# feather-v1.net
KiCad netlist of a schematic drawn in EAGLE
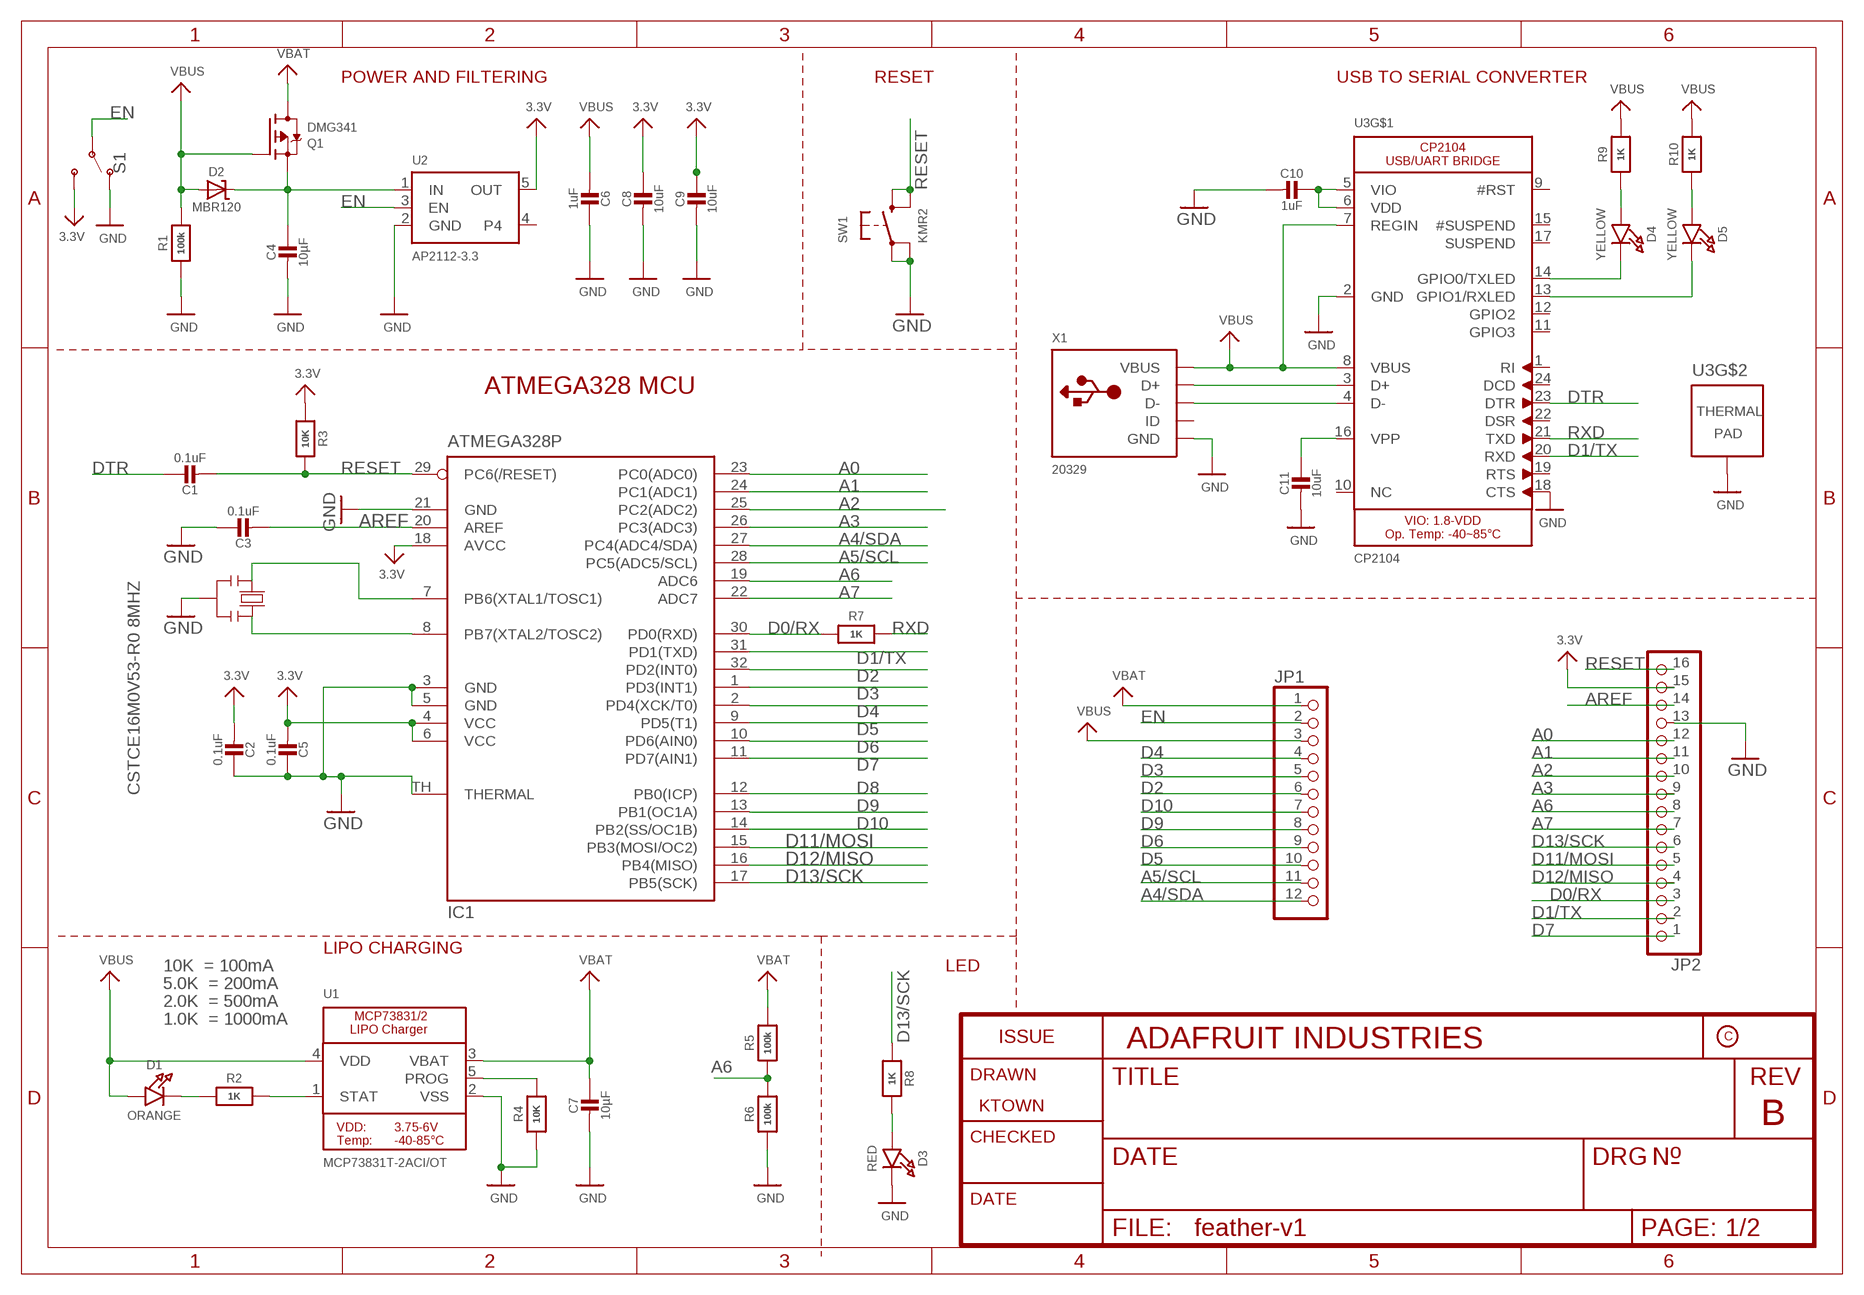
[diagram p0: schematic, sheet 1]
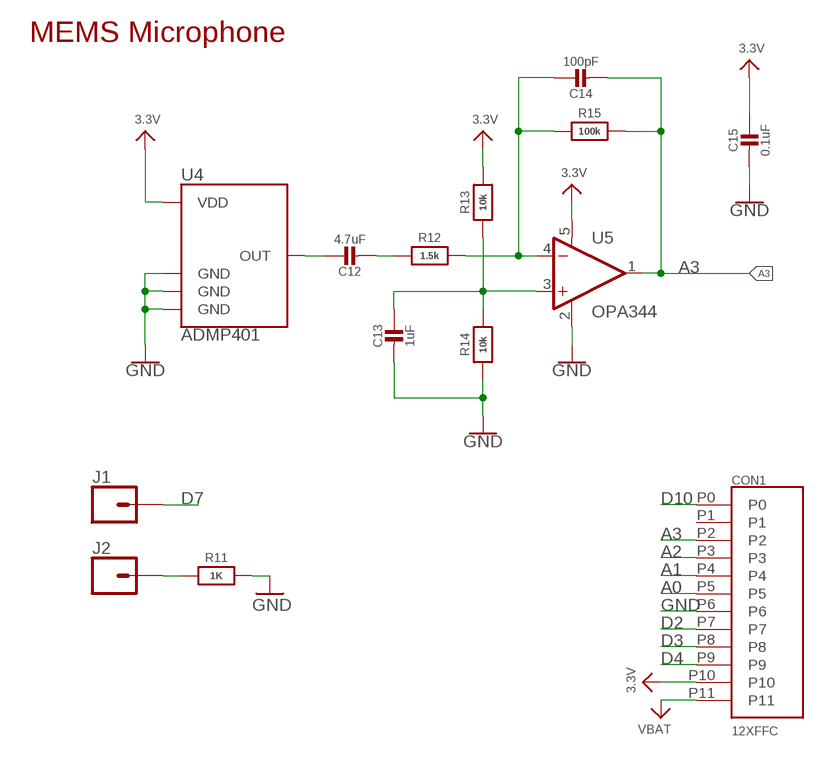
[diagram p1: schematic, sheet 2]

(export (version "E")
  (design (tool "Eeschema 10.0.6"))
  (components
    (comp (ref "C12")
      (value "4.7uF")
      (footprint "eagle-import:_0603MP")
      (libsource (lib "eagle-import") (part "CAP_CERAMIC_0603MP"))
    )
    (comp (ref "C13")
      (value "1uF")
      (footprint "eagle-import:_0603MP")
      (libsource (lib "eagle-import") (part "CAP_CERAMIC_0603MP"))
    )
    (comp (ref "C14")
      (value "100pF")
      (footprint "eagle-import:_0603MP")
      (libsource (lib "eagle-import") (part "CAP_CERAMIC_0603MP"))
    )
    (comp (ref "C15")
      (value "0.1uF")
      (footprint "eagle-import:_0603MP")
      (libsource (lib "eagle-import") (part "CAP_CERAMIC_0603MP"))
    )
    (comp (ref "CON1")
      (value "12XFFC")
      (footprint "eagle-import:15166-0117")
      (libsource (lib "eagle-import") (part "12XFFC"))
    )
    (comp (ref "J1")
      (value "CONN_01PTH_NO_SILK_YES_STOP")
      (footprint "eagle-import:1X01_NO_SILK")
      (libsource (lib "eagle-import") (part "CONN_01PTH_NO_SILK_YES_STOP"))
    )
    (comp (ref "J2")
      (value "CONN_01PTH_NO_SILK_YES_STOP")
      (footprint "eagle-import:1X01_NO_SILK")
      (libsource (lib "eagle-import") (part "CONN_01PTH_NO_SILK_YES_STOP"))
    )
    (comp (ref "R11")
      (value "1K")
      (footprint "eagle-import:_0603MP")
      (libsource (lib "eagle-import") (part "RESISTOR_0603MP"))
    )
    (comp (ref "R12")
      (value "1.5k")
      (footprint "eagle-import:_0603MP")
      (libsource (lib "eagle-import") (part "RESISTOR_0603MP"))
    )
    (comp (ref "R13")
      (value "10k")
      (footprint "eagle-import:_0603MP")
      (libsource (lib "eagle-import") (part "RESISTOR_0603MP"))
    )
    (comp (ref "R14")
      (value "10k")
      (footprint "eagle-import:_0603MP")
      (libsource (lib "eagle-import") (part "RESISTOR_0603MP"))
    )
    (comp (ref "R15")
      (value "100k")
      (footprint "eagle-import:_0603MP")
      (libsource (lib "eagle-import") (part "RESISTOR_0603MP"))
    )
    (comp (ref "U4")
      (value "ADMP401")
      (footprint "eagle-import:ADMP401")
      (libsource (lib "eagle-import") (part "ADMP401"))
    )
    (comp (ref "U5")
      (value "OPA344")
      (footprint "eagle-import:SOT23-5")
      (libsource (lib "eagle-import") (part "OPA344"))
    )
    (comp (ref "C1")
      (value "0.1uF")
      (footprint "eagle-import:_0603MP")
      (libsource (lib "eagle-import") (part "CAP_CERAMIC_0603MP"))
    )
    (comp (ref "C2")
      (value "0.1uF")
      (footprint "eagle-import:_0603MP")
      (libsource (lib "eagle-import") (part "CAP_CERAMIC_0603MP"))
    )
    (comp (ref "C3")
      (value "0.1uF")
      (footprint "eagle-import:_0603MP")
      (libsource (lib "eagle-import") (part "CAP_CERAMIC_0603MP"))
    )
    (comp (ref "C4")
      (value "10µF")
      (footprint "eagle-import:_0603MP")
      (libsource (lib "eagle-import") (part "CAP_CERAMIC_0603MP"))
    )
    (comp (ref "C5")
      (value "0.1uF")
      (footprint "eagle-import:_0603MP")
      (libsource (lib "eagle-import") (part "CAP_CERAMIC_0603MP"))
    )
    (comp (ref "C6")
      (value "1uF")
      (footprint "eagle-import:_0603MP")
      (libsource (lib "eagle-import") (part "CAP_CERAMIC_0603MP"))
    )
    (comp (ref "C7")
      (value "10µF")
      (footprint "eagle-import:_0603MP")
      (libsource (lib "eagle-import") (part "CAP_CERAMIC_0603MP"))
    )
    (comp (ref "C8")
      (value "10uF")
      (footprint "eagle-import:_0603MP")
      (libsource (lib "eagle-import") (part "CAP_CERAMIC_0603MP"))
    )
    (comp (ref "C9")
      (value "10uF")
      (footprint "eagle-import:_0603MP")
      (libsource (lib "eagle-import") (part "CAP_CERAMIC_0603MP"))
    )
    (comp (ref "C10")
      (value "1uF")
      (footprint "eagle-import:_0603MP")
      (libsource (lib "eagle-import") (part "CAP_CERAMIC_0603MP"))
    )
    (comp (ref "C11")
      (value "10uF")
      (footprint "eagle-import:_0603MP")
      (libsource (lib "eagle-import") (part "CAP_CERAMIC_0603MP"))
    )
    (comp (ref "D1")
      (value "ORANGE")
      (footprint "eagle-import:CHIPLED_0603_NOOUTLINE")
      (libsource (lib "eagle-import") (part "LED0603_NOOUTLINE"))
    )
    (comp (ref "D2")
      (value "MBR120")
      (footprint "eagle-import:SOD-523")
      (libsource (lib "eagle-import") (part "DIODE-SCHOTTKYSOD-523"))
    )
    (comp (ref "D3")
      (value "RED")
      (footprint "eagle-import:CHIPLED_0603_NOOUTLINE")
      (libsource (lib "eagle-import") (part "LED0603_NOOUTLINE"))
    )
    (comp (ref "D4")
      (value "YELLOW")
      (footprint "eagle-import:CHIPLED_0603_NOOUTLINE")
      (libsource (lib "eagle-import") (part "LED0603_NOOUTLINE"))
    )
    (comp (ref "D5")
      (value "YELLOW")
      (footprint "eagle-import:CHIPLED_0603_NOOUTLINE")
      (libsource (lib "eagle-import") (part "LED0603_NOOUTLINE"))
    )
    (comp (ref "IC1")
      (value "ATMEGA328P")
      (footprint "eagle-import:MLF32-TH")
      (fields (field (name "MPN") "ATMEGA88PA-MU"))
      (libsource (lib "eagle-import") (part "MEGA8-MI"))
    )
    (comp (ref "JP1")
      (value "HEADER-1X12")
      (footprint "eagle-import:1X12_ROUND")
      (libsource (lib "eagle-import") (part "HEADER-1X12"))
    )
    (comp (ref "JP2")
      (value "HEADER-1X16ROUND")
      (footprint "eagle-import:1X16_ROUND")
      (libsource (lib "eagle-import") (part "HEADER-1X16ROUND"))
    )
    (comp (ref "Q1")
      (value "DMG341")
      (footprint "eagle-import:SOT23-R")
      (libsource (lib "eagle-import") (part "MOSFET-P"))
    )
    (comp (ref "R1")
      (value "100k")
      (footprint "eagle-import:_0603MP")
      (libsource (lib "eagle-import") (part "RESISTOR_0603MP"))
    )
    (comp (ref "R2")
      (value "1K")
      (footprint "eagle-import:_0603MP")
      (libsource (lib "eagle-import") (part "RESISTOR_0603MP"))
    )
    (comp (ref "R3")
      (value "10K")
      (footprint "eagle-import:_0603MP")
      (libsource (lib "eagle-import") (part "RESISTOR_0603MP"))
    )
    (comp (ref "R4")
      (value "10K")
      (footprint "eagle-import:_0603MP")
      (libsource (lib "eagle-import") (part "RESISTOR_0603MP"))
    )
    (comp (ref "R5")
      (value "100k")
      (footprint "eagle-import:_0603MP")
      (libsource (lib "eagle-import") (part "RESISTOR_0603MP"))
    )
    (comp (ref "R6")
      (value "100k")
      (footprint "eagle-import:_0603MP")
      (libsource (lib "eagle-import") (part "RESISTOR_0603MP"))
    )
    (comp (ref "R7")
      (value "1K")
      (footprint "eagle-import:_0603MP")
      (libsource (lib "eagle-import") (part "RESISTOR_0603MP"))
    )
    (comp (ref "R8")
      (value "1K")
      (footprint "eagle-import:_0603MP")
      (libsource (lib "eagle-import") (part "RESISTOR_0603MP"))
    )
    (comp (ref "R9")
      (value "1K")
      (footprint "eagle-import:_0603MP")
      (libsource (lib "eagle-import") (part "RESISTOR_0603MP"))
    )
    (comp (ref "R10")
      (value "1K")
      (footprint "eagle-import:_0603MP")
      (libsource (lib "eagle-import") (part "RESISTOR_0603MP"))
    )
    (comp (ref "S1")
      (value "SWITCH-SPDT-SMD-RIGHT-ANGLE")
      (footprint "eagle-import:SWITCH_SPST_SMD_A")
      (libsource (lib "eagle-import") (part "SWITCH-SPDT-SMD-RIGHT-ANGLE"))
    )
    (comp (ref "SW1")
      (value "KMR2")
      (footprint "eagle-import:BTN_KMR2_4.6X2.8")
      (libsource (lib "eagle-import") (part "SWITCH_TACT_SMT4.6X2.8"))
    )
    (comp (ref "U1")
      (value "MCP73831T-2ACI/OT")
      (footprint "eagle-import:SOT23-5")
      (libsource (lib "eagle-import") (part "MCP73831/2"))
    )
    (comp (ref "U2")
      (value "AP2112-3.3")
      (footprint "eagle-import:SOT23-5")
      (libsource (lib "eagle-import") (part "VREG_SOT23-5"))
    )
    (comp (ref "U3")
      (value "CP2104")
      (footprint "eagle-import:QFN24_4MM_SMSC")
      (libsource (lib "eagle-import") (part "CP2104"))
    )
    (comp (ref "X1")
      (value "20329")
      (footprint "eagle-import:4UCONN_20329_V2")
      (libsource (lib "eagle-import") (part "USB_MICRO_20329_V2"))
    )
    (comp (ref "Y1")
      (value "CSTCE16M0V53-R0 8MHZ")
      (footprint "eagle-import:RESONATOR")
      (libsource (lib "eagle-import") (part "RESONATORMU"))
    )
  )
  (nets
    (net (code "1") (name "3.3V") (class "Default")
      (node (ref "C15") (pin "1") (pinfunction "1_1") (pintype "passive"))
      (node (ref "C2") (pin "2") (pinfunction "2_2") (pintype "passive"))
      (node (ref "C5") (pin "2") (pinfunction "2_2") (pintype "passive"))
      (node (ref "C8") (pin "1") (pinfunction "1_1") (pintype "passive"))
      (node (ref "C9") (pin "1") (pinfunction "1_1") (pintype "passive"))
      (node (ref "CON1") (pin "P10") (pinfunction "P10_P10") (pintype "bidirectional"))
      (node (ref "IC1") (pin "18") (pinfunction "AVCC_18") (pintype "power_in"))
      (node (ref "IC1") (pin "4") (pinfunction "VCC_4") (pintype "power_in"))
      (node (ref "IC1") (pin "6") (pinfunction "VCC_6") (pintype "power_in"))
      (node (ref "JP2") (pin "15") (pinfunction "15_15") (pintype "passive"))
      (node (ref "R13") (pin "2") (pinfunction "2_2") (pintype "passive"))
      (node (ref "R3") (pin "2") (pinfunction "2_2") (pintype "passive"))
      (node (ref "S1") (pin "3") (pinfunction "S_3") (pintype "passive"))
      (node (ref "U2") (pin "5") (pinfunction "OUT_5") (pintype "power_in"))
      (node (ref "U4") (pin "5") (pinfunction "VDD_5") (pintype "bidirectional"))
      (node (ref "U5") (pin "5") (pinfunction "V+_5") (pintype "power_in"))
    )
    (net (code "2") (name "A0") (class "Default")
      (node (ref "CON1") (pin "P5") (pinfunction "P5_P5") (pintype "bidirectional"))
      (node (ref "IC1") (pin "23") (pinfunction "PC0(ADC0)_23") (pintype "bidirectional"))
      (node (ref "JP2") (pin "12") (pinfunction "12_12") (pintype "passive"))
    )
    (net (code "3") (name "A1") (class "Default")
      (node (ref "CON1") (pin "P4") (pinfunction "P4_P4") (pintype "bidirectional"))
      (node (ref "IC1") (pin "24") (pinfunction "PC1(ADC1)_24") (pintype "bidirectional"))
      (node (ref "JP2") (pin "11") (pinfunction "11_11") (pintype "passive"))
    )
    (net (code "4") (name "A2") (class "Default")
      (node (ref "CON1") (pin "P3") (pinfunction "P3_P3") (pintype "bidirectional"))
      (node (ref "IC1") (pin "25") (pinfunction "PC2(ADC2)_25") (pintype "bidirectional"))
      (node (ref "JP2") (pin "10") (pinfunction "10_10") (pintype "passive"))
    )
    (net (code "5") (name "A3") (class "Default")
      (node (ref "C14") (pin "2") (pinfunction "2_2") (pintype "passive"))
      (node (ref "CON1") (pin "P2") (pinfunction "P2_P2") (pintype "bidirectional"))
      (node (ref "IC1") (pin "26") (pinfunction "PC3(ADC3)_26") (pintype "bidirectional"))
      (node (ref "JP2") (pin "9") (pinfunction "9_9") (pintype "passive"))
      (node (ref "R15") (pin "2") (pinfunction "2_2") (pintype "passive"))
      (node (ref "U5") (pin "1") (pinfunction "OUT_1") (pintype "output"))
    )
    (net (code "6") (name "A4{slash}SDA") (class "Default")
      (node (ref "IC1") (pin "27") (pinfunction "PC4(ADC4/SDA)_27") (pintype "bidirectional"))
      (node (ref "JP1") (pin "12") (pinfunction "12_12") (pintype "passive"))
    )
    (net (code "7") (name "A5{slash}SCL") (class "Default")
      (node (ref "IC1") (pin "28") (pinfunction "PC5(ADC5/SCL)_28") (pintype "bidirectional"))
      (node (ref "JP1") (pin "11") (pinfunction "11_11") (pintype "passive"))
    )
    (net (code "8") (name "A6") (class "Default")
      (node (ref "IC1") (pin "19") (pinfunction "ADC6_19") (pintype "bidirectional"))
      (node (ref "JP2") (pin "8") (pinfunction "8_8") (pintype "passive"))
      (node (ref "R5") (pin "1") (pinfunction "1_1") (pintype "passive"))
      (node (ref "R6") (pin "2") (pinfunction "2_2") (pintype "passive"))
    )
    (net (code "9") (name "A7") (class "Default")
      (node (ref "IC1") (pin "22") (pinfunction "ADC7_22") (pintype "bidirectional"))
      (node (ref "JP2") (pin "7") (pinfunction "7_7") (pintype "passive"))
    )
    (net (code "10") (name "AREF") (class "Default")
      (node (ref "C3") (pin "2") (pinfunction "2_2") (pintype "passive"))
      (node (ref "IC1") (pin "20") (pinfunction "AREF_20") (pintype "passive"))
      (node (ref "JP2") (pin "14") (pinfunction "14_14") (pintype "passive"))
    )
    (net (code "11") (name "D0{slash}RX") (class "Default")
      (node (ref "IC1") (pin "30") (pinfunction "PD0(RXD)_30") (pintype "bidirectional"))
      (node (ref "JP2") (pin "3") (pinfunction "3_3") (pintype "passive"))
      (node (ref "R7") (pin "1") (pinfunction "1_1") (pintype "passive"))
    )
    (net (code "12") (name "D1{slash}TX") (class "Default")
      (node (ref "IC1") (pin "31") (pinfunction "PD1(TXD)_31") (pintype "bidirectional"))
      (node (ref "JP2") (pin "2") (pinfunction "2_2") (pintype "passive"))
      (node (ref "U3") (pin "20") (pinfunction "RXD_20") (pintype "input"))
    )
    (net (code "13") (name "D2") (class "Default")
      (node (ref "CON1") (pin "P7") (pinfunction "P7_P7") (pintype "bidirectional"))
      (node (ref "IC1") (pin "32") (pinfunction "PD2(INT0)_32") (pintype "bidirectional"))
      (node (ref "JP1") (pin "6") (pinfunction "6_6") (pintype "passive"))
    )
    (net (code "14") (name "D3") (class "Default")
      (node (ref "CON1") (pin "P8") (pinfunction "P8_P8") (pintype "bidirectional"))
      (node (ref "IC1") (pin "1") (pinfunction "PD3(INT1)_1") (pintype "bidirectional"))
      (node (ref "JP1") (pin "5") (pinfunction "5_5") (pintype "passive"))
    )
    (net (code "15") (name "D4") (class "Default")
      (node (ref "CON1") (pin "P9") (pinfunction "P9_P9") (pintype "bidirectional"))
      (node (ref "IC1") (pin "2") (pinfunction "PD4(XCK/T0)_2") (pintype "bidirectional"))
      (node (ref "JP1") (pin "4") (pinfunction "4_4") (pintype "passive"))
    )
    (net (code "16") (name "D5") (class "Default")
      (node (ref "IC1") (pin "9") (pinfunction "PD5(T1)_9") (pintype "bidirectional"))
      (node (ref "JP1") (pin "10") (pinfunction "10_10") (pintype "passive"))
    )
    (net (code "17") (name "D6") (class "Default")
      (node (ref "IC1") (pin "10") (pinfunction "PD6(AIN0)_10") (pintype "bidirectional"))
      (node (ref "JP1") (pin "9") (pinfunction "9_9") (pintype "passive"))
    )
    (net (code "18") (name "D7") (class "Default")
      (node (ref "IC1") (pin "11") (pinfunction "PD7(AIN1)_11") (pintype "bidirectional"))
      (node (ref "J1") (pin "1") (pinfunction "1_1") (pintype "passive"))
      (node (ref "JP2") (pin "1") (pinfunction "1_1") (pintype "passive"))
    )
    (net (code "19") (name "D8") (class "Default")
      (node (ref "IC1") (pin "12") (pinfunction "PB0(ICP)_12") (pintype "bidirectional"))
    )
    (net (code "20") (name "D9") (class "Default")
      (node (ref "IC1") (pin "13") (pinfunction "PB1(OC1A)_13") (pintype "bidirectional"))
      (node (ref "JP1") (pin "8") (pinfunction "8_8") (pintype "passive"))
    )
    (net (code "21") (name "D10") (class "Default")
      (node (ref "CON1") (pin "P0") (pinfunction "P0_P0") (pintype "bidirectional"))
      (node (ref "IC1") (pin "14") (pinfunction "PB2(SS/OC1B)_14") (pintype "bidirectional"))
      (node (ref "JP1") (pin "7") (pinfunction "7_7") (pintype "passive"))
    )
    (net (code "22") (name "D11{slash}MOSI") (class "Default")
      (node (ref "IC1") (pin "15") (pinfunction "PB3(MOSI/OC2)_15") (pintype "bidirectional"))
      (node (ref "JP2") (pin "5") (pinfunction "5_5") (pintype "passive"))
    )
    (net (code "23") (name "D12{slash}MISO") (class "Default")
      (node (ref "IC1") (pin "16") (pinfunction "PB4(MISO)_16") (pintype "bidirectional"))
      (node (ref "JP2") (pin "4") (pinfunction "4_4") (pintype "passive"))
    )
    (net (code "24") (name "D13{slash}SCK") (class "Default")
      (node (ref "IC1") (pin "17") (pinfunction "PB5(SCK)_17") (pintype "bidirectional"))
      (node (ref "JP2") (pin "6") (pinfunction "6_6") (pintype "passive"))
      (node (ref "R8") (pin "1") (pinfunction "1_1") (pintype "passive"))
    )
    (net (code "25") (name "DTR") (class "Default")
      (node (ref "C1") (pin "1") (pinfunction "1_1") (pintype "passive"))
      (node (ref "U3") (pin "23") (pinfunction "DTR_23") (pintype "output"))
    )
    (net (code "26") (name "EN") (class "Default")
      (node (ref "JP1") (pin "2") (pinfunction "2_2") (pintype "passive"))
      (node (ref "S1") (pin "2") (pinfunction "P_2") (pintype "passive"))
      (node (ref "U2") (pin "3") (pinfunction "EN_3") (pintype "input"))
    )
    (net (code "27") (name "GND") (class "Default")
      (node (ref "C10") (pin "2") (pinfunction "2_2") (pintype "passive"))
      (node (ref "C11") (pin "2") (pinfunction "2_2") (pintype "passive"))
      (node (ref "C13") (pin "2") (pinfunction "2_2") (pintype "passive"))
      (node (ref "C15") (pin "2") (pinfunction "2_2") (pintype "passive"))
      (node (ref "C2") (pin "1") (pinfunction "1_1") (pintype "passive"))
      (node (ref "C3") (pin "1") (pinfunction "1_1") (pintype "passive"))
      (node (ref "C4") (pin "2") (pinfunction "2_2") (pintype "passive"))
      (node (ref "C5") (pin "1") (pinfunction "1_1") (pintype "passive"))
      (node (ref "C6") (pin "1") (pinfunction "1_1") (pintype "passive"))
      (node (ref "C7") (pin "2") (pinfunction "2_2") (pintype "passive"))
      (node (ref "C8") (pin "2") (pinfunction "2_2") (pintype "passive"))
      (node (ref "C9") (pin "2") (pinfunction "2_2") (pintype "passive"))
      (node (ref "CON1") (pin "P6") (pinfunction "P6_P6") (pintype "bidirectional"))
      (node (ref "D3") (pin "C") (pinfunction "C_C") (pintype "passive"))
      (node (ref "IC1") (pin "21") (pinfunction "GND_21") (pintype "power_in"))
      (node (ref "IC1") (pin "3") (pinfunction "GND_3") (pintype "power_in"))
      (node (ref "IC1") (pin "5") (pinfunction "GND_5") (pintype "power_in"))
      (node (ref "IC1") (pin "TH") (pinfunction "THERMAL_TH") (pintype "passive"))
      (node (ref "JP2") (pin "13") (pinfunction "13_13") (pintype "passive"))
      (node (ref "R1") (pin "1") (pinfunction "1_1") (pintype "passive"))
      (node (ref "R11") (pin "2") (pinfunction "2_2") (pintype "passive"))
      (node (ref "R14") (pin "1") (pinfunction "1_1") (pintype "passive"))
      (node (ref "R4") (pin "1") (pinfunction "1_1") (pintype "passive"))
      (node (ref "R6") (pin "1") (pinfunction "1_1") (pintype "passive"))
      (node (ref "S1") (pin "1") (pinfunction "O_1") (pintype "passive"))
      (node (ref "SW1") (pin "A") (pinfunction "P_A") (pintype "passive"))
      (node (ref "SW1") (pin "A'") (pinfunction "P1_A'") (pintype "passive"))
      (node (ref "U1") (pin "2") (pinfunction "VSS_2") (pintype "power_in"))
      (node (ref "U2") (pin "2") (pinfunction "GND_2") (pintype "power_in"))
      (node (ref "U3") (pin "18") (pinfunction "CTS_18") (pintype "input"))
      (node (ref "U3") (pin "2") (pinfunction "GND_2") (pintype "power_in"))
      (node (ref "U3") (pin "THERM") (pinfunction "TP_THERM") (pintype "power_in"))
      (node (ref "U4") (pin "2") (pinfunction "GND_2") (pintype "bidirectional"))
      (node (ref "U4") (pin "4") (pinfunction "GND_4") (pintype "bidirectional"))
      (node (ref "U4") (pin "6") (pinfunction "GND_6") (pintype "bidirectional"))
      (node (ref "U5") (pin "2") (pinfunction "V-_2") (pintype "power_in"))
      (node (ref "X1") (pin "BASE@1") (pinfunction "GND_BASE@1") (pintype "power_in"))
      (node (ref "X1") (pin "BASE@2") (pinfunction "GND_BASE@2") (pintype "power_in"))
      (node (ref "X1") (pin "GND") (pinfunction "GND_GND") (pintype "power_in"))
      (node (ref "X1") (pin "SPRT@1") (pinfunction "GND_SPRT@1") (pintype "power_in"))
      (node (ref "X1") (pin "SPRT@2") (pinfunction "GND_SPRT@2") (pintype "power_in"))
      (node (ref "X1") (pin "SPRT@3") (pinfunction "GND_SPRT@3") (pintype "power_in"))
      (node (ref "X1") (pin "SPRT@4") (pinfunction "GND_SPRT@4") (pintype "power_in"))
      (node (ref "Y1") (pin "2") (pinfunction "2_2") (pintype "passive"))
    )
    (net (code "28") (name "Net-(C12-Pad2)") (class "Default")
      (node (ref "C12") (pin "2") (pinfunction "2_2") (pintype "passive"))
      (node (ref "R12") (pin "1") (pinfunction "1_1") (pintype "passive"))
    )
    (net (code "29") (name "Net-(D1-PadC)") (class "Default")
      (node (ref "D1") (pin "C") (pinfunction "C_C") (pintype "passive"))
      (node (ref "R2") (pin "1") (pinfunction "1_1") (pintype "passive"))
    )
    (net (code "30") (name "Net-(D2-C)") (class "Default")
      (node (ref "C4") (pin "1") (pinfunction "1_1") (pintype "passive"))
      (node (ref "D2") (pin "K") (pinfunction "C_K") (pintype "passive"))
      (node (ref "Q1") (pin "2") (pinfunction "S_2") (pintype "passive"))
      (node (ref "U2") (pin "1") (pinfunction "IN_1") (pintype "power_in"))
    )
    (net (code "31") (name "Net-(D3-PadA)") (class "Default")
      (node (ref "D3") (pin "A") (pinfunction "A_A") (pintype "passive"))
      (node (ref "R8") (pin "2") (pinfunction "2_2") (pintype "passive"))
    )
    (net (code "32") (name "Net-(D4-PadA)") (class "Default")
      (node (ref "D4") (pin "A") (pinfunction "A_A") (pintype "passive"))
      (node (ref "R9") (pin "1") (pinfunction "1_1") (pintype "passive"))
    )
    (net (code "33") (name "Net-(D5-PadA)") (class "Default")
      (node (ref "D5") (pin "A") (pinfunction "A_A") (pintype "passive"))
      (node (ref "R10") (pin "1") (pinfunction "1_1") (pintype "passive"))
    )
    (net (code "34") (name "Net-(IC1-PB6(XTAL1{slash}TOSC1))") (class "Default")
      (node (ref "IC1") (pin "7") (pinfunction "PB6(XTAL1/TOSC1)_7") (pintype "bidirectional"))
      (node (ref "Y1") (pin "1") (pinfunction "1_1") (pintype "passive"))
    )
    (net (code "35") (name "Net-(IC1-PB7(XTAL2{slash}TOSC2))") (class "Default")
      (node (ref "IC1") (pin "8") (pinfunction "PB7(XTAL2/TOSC2)_8") (pintype "bidirectional"))
      (node (ref "Y1") (pin "3") (pinfunction "3_3") (pintype "passive"))
    )
    (net (code "36") (name "Net-(J2-Pad1)") (class "Default")
      (node (ref "J2") (pin "1") (pinfunction "1_1") (pintype "passive"))
      (node (ref "R11") (pin "1") (pinfunction "1_1") (pintype "passive"))
    )
    (net (code "37") (name "Net-(U1-PROG)") (class "Default")
      (node (ref "R4") (pin "2") (pinfunction "2_2") (pintype "passive"))
      (node (ref "U1") (pin "5") (pinfunction "PROG_5") (pintype "input"))
    )
    (net (code "38") (name "Net-(U1-STAT)") (class "Default")
      (node (ref "R2") (pin "2") (pinfunction "2_2") (pintype "passive"))
      (node (ref "U1") (pin "1") (pinfunction "STAT_1") (pintype "output"))
    )
    (net (code "39") (name "Net-(U3A-D+)") (class "Default")
      (node (ref "U3") (pin "3") (pinfunction "D+_3") (pintype "bidirectional"))
      (node (ref "X1") (pin "D+") (pinfunction "D+_D+") (pintype "bidirectional"))
    )
    (net (code "40") (name "Net-(U3A-D-)") (class "Default")
      (node (ref "U3") (pin "4") (pinfunction "D-_4") (pintype "bidirectional"))
      (node (ref "X1") (pin "D-") (pinfunction "D-_D-") (pintype "bidirectional"))
    )
    (net (code "41") (name "Net-(U3A-GPIO0{slash}TXLED)") (class "Default")
      (node (ref "D4") (pin "C") (pinfunction "C_C") (pintype "passive"))
      (node (ref "U3") (pin "14") (pinfunction "GPIO0/TXLED_14") (pintype "bidirectional"))
    )
    (net (code "42") (name "Net-(U3A-GPIO1{slash}RXLED)") (class "Default")
      (node (ref "D5") (pin "C") (pinfunction "C_C") (pintype "passive"))
      (node (ref "U3") (pin "13") (pinfunction "GPIO1/RXLED_13") (pintype "bidirectional"))
    )
    (net (code "43") (name "Net-(U3A-VDD)") (class "Default")
      (node (ref "C10") (pin "1") (pinfunction "1_1") (pintype "passive"))
      (node (ref "U3") (pin "5") (pinfunction "VIO_5") (pintype "power_in"))
      (node (ref "U3") (pin "6") (pinfunction "VDD_6") (pintype "power_in"))
    )
    (net (code "44") (name "Net-(U3A-VPP)") (class "Default")
      (node (ref "C11") (pin "1") (pinfunction "1_1") (pintype "passive"))
      (node (ref "U3") (pin "16") (pinfunction "VPP_16") (pintype "bidirectional"))
    )
    (net (code "45") (name "Net-(U4-OUT)") (class "Default")
      (node (ref "C12") (pin "1") (pinfunction "1_1") (pintype "passive"))
      (node (ref "U4") (pin "1") (pinfunction "OUT_1") (pintype "bidirectional"))
    )
    (net (code "46") (name "Net-(U5-+IN)") (class "Default")
      (node (ref "C13") (pin "1") (pinfunction "1_1") (pintype "passive"))
      (node (ref "R13") (pin "1") (pinfunction "1_1") (pintype "passive"))
      (node (ref "R14") (pin "2") (pinfunction "2_2") (pintype "passive"))
      (node (ref "U5") (pin "3") (pinfunction "+IN_3") (pintype "input"))
    )
    (net (code "47") (name "Net-(U5--IN)") (class "Default")
      (node (ref "C14") (pin "1") (pinfunction "1_1") (pintype "passive"))
      (node (ref "R12") (pin "2") (pinfunction "2_2") (pintype "passive"))
      (node (ref "R15") (pin "1") (pinfunction "1_1") (pintype "passive"))
      (node (ref "U5") (pin "4") (pinfunction "-IN_4") (pintype "input"))
    )
    (net (code "48") (name "RESET") (class "Default")
      (node (ref "C1") (pin "2") (pinfunction "2_2") (pintype "passive"))
      (node (ref "IC1") (pin "29") (pinfunction "PC6(/RESET)_29") (pintype "bidirectional"))
      (node (ref "JP2") (pin "16") (pinfunction "16_16") (pintype "passive"))
      (node (ref "R3") (pin "1") (pinfunction "1_1") (pintype "passive"))
      (node (ref "SW1") (pin "B") (pinfunction "S_B") (pintype "passive"))
      (node (ref "SW1") (pin "B'") (pinfunction "S1_B'") (pintype "passive"))
    )
    (net (code "49") (name "RXD") (class "Default")
      (node (ref "R7") (pin "2") (pinfunction "2_2") (pintype "passive"))
      (node (ref "U3") (pin "21") (pinfunction "TXD_21") (pintype "output"))
    )
    (net (code "50") (name "VBAT") (class "Default")
      (node (ref "C7") (pin "1") (pinfunction "1_1") (pintype "passive"))
      (node (ref "CON1") (pin "P11") (pinfunction "P11_P11") (pintype "bidirectional"))
      (node (ref "JP1") (pin "1") (pinfunction "1_1") (pintype "passive"))
      (node (ref "Q1") (pin "3") (pinfunction "D_3") (pintype "passive"))
      (node (ref "R5") (pin "2") (pinfunction "2_2") (pintype "passive"))
      (node (ref "U1") (pin "3") (pinfunction "VBAT_3") (pintype "power_in"))
    )
    (net (code "51") (name "VBUS") (class "Default")
      (node (ref "C6") (pin "2") (pinfunction "2_2") (pintype "passive"))
      (node (ref "D1") (pin "A") (pinfunction "A_A") (pintype "passive"))
      (node (ref "D2") (pin "A") (pinfunction "A_A") (pintype "passive"))
      (node (ref "JP1") (pin "3") (pinfunction "3_3") (pintype "passive"))
      (node (ref "Q1") (pin "1") (pinfunction "G_1") (pintype "passive"))
      (node (ref "R1") (pin "2") (pinfunction "2_2") (pintype "passive"))
      (node (ref "R10") (pin "2") (pinfunction "2_2") (pintype "passive"))
      (node (ref "R9") (pin "2") (pinfunction "2_2") (pintype "passive"))
      (node (ref "U1") (pin "4") (pinfunction "VDD_4") (pintype "power_in"))
      (node (ref "U3") (pin "7") (pinfunction "REGIN_7") (pintype "power_in"))
      (node (ref "U3") (pin "8") (pinfunction "VBUS_8") (pintype "power_in"))
      (node (ref "X1") (pin "VBUS") (pinfunction "VBUS_VBUS") (pintype "power_in"))
    )
    (net (code "52") (name "unconnected-(CON1-PadP1)") (class "Default")
      (node (ref "CON1") (pin "P1") (pinfunction "P1_P1") (pintype "bidirectional"))
    )
    (net (code "53") (name "unconnected-(U2-P4-Pad4)") (class "Default")
      (node (ref "U2") (pin "4") (pinfunction "P4_4") (pintype "bidirectional"))
    )
    (net (code "54") (name "unconnected-(U3A-#RST-Pad9)") (class "Default")
      (node (ref "U3") (pin "9") (pinfunction "#RST_9") (pintype "bidirectional"))
    )
    (net (code "55") (name "unconnected-(U3A-#SUSPEND-Pad15)") (class "Default")
      (node (ref "U3") (pin "15") (pinfunction "#SUSPEND_15") (pintype "output"))
    )
    (net (code "56") (name "unconnected-(U3A-DCD-Pad24)") (class "Default")
      (node (ref "U3") (pin "24") (pinfunction "DCD_24") (pintype "input"))
    )
    (net (code "57") (name "unconnected-(U3A-DSR-Pad22)") (class "Default")
      (node (ref "U3") (pin "22") (pinfunction "DSR_22") (pintype "input"))
    )
    (net (code "58") (name "unconnected-(U3A-GPIO2-Pad12)") (class "Default")
      (node (ref "U3") (pin "12") (pinfunction "GPIO2_12") (pintype "bidirectional"))
    )
    (net (code "59") (name "unconnected-(U3A-GPIO3-Pad11)") (class "Default")
      (node (ref "U3") (pin "11") (pinfunction "GPIO3_11") (pintype "bidirectional"))
    )
    (net (code "60") (name "unconnected-(U3A-NC-Pad10)") (class "Default")
      (node (ref "U3") (pin "10") (pinfunction "NC_10") (pintype "no_connect"))
    )
    (net (code "61") (name "unconnected-(U3A-RI-Pad1)") (class "Default")
      (node (ref "U3") (pin "1") (pinfunction "RI_1") (pintype "input"))
    )
    (net (code "62") (name "unconnected-(U3A-RTS-Pad19)") (class "Default")
      (node (ref "U3") (pin "19") (pinfunction "RTS_19") (pintype "output"))
    )
    (net (code "63") (name "unconnected-(U3A-SUSPEND-Pad17)") (class "Default")
      (node (ref "U3") (pin "17") (pinfunction "SUSPEND_17") (pintype "output"))
    )
    (net (code "64") (name "unconnected-(X1-PadID)") (class "Default")
      (node (ref "X1") (pin "ID") (pinfunction "ID_ID") (pintype "bidirectional"))
    )
  )
)
